# Connect.net
KiCad netlist of a schematic drawn in Altium Designer
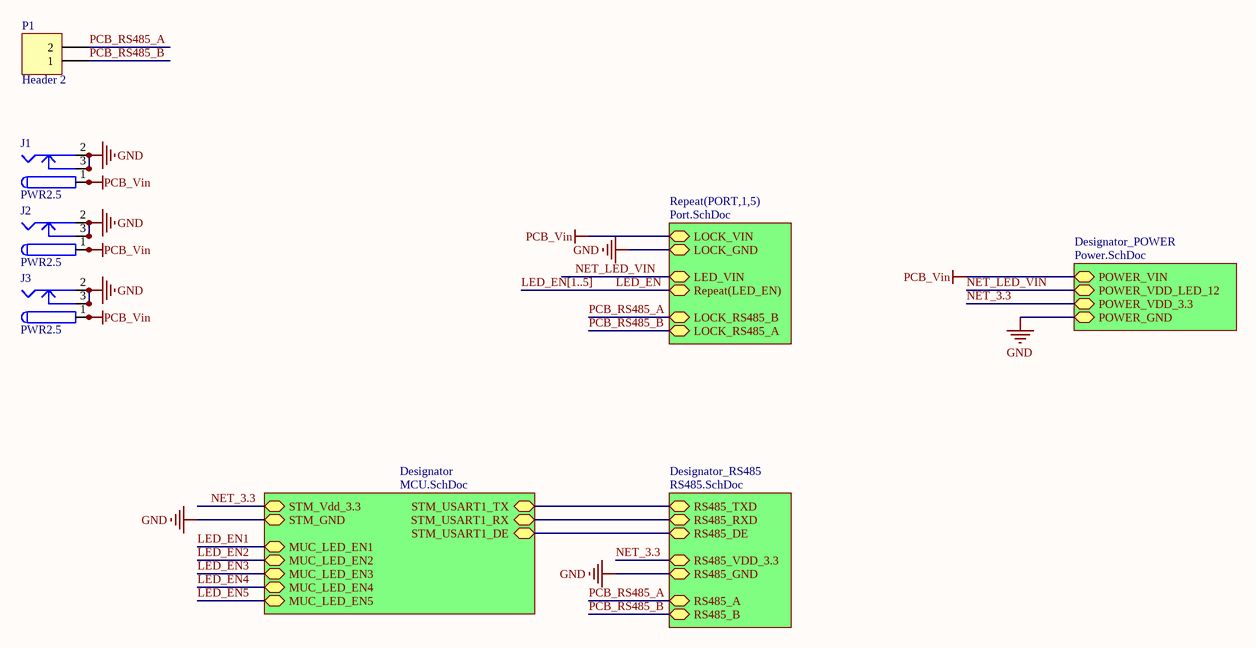
[diagram p0: Connect.SchDoc]

(export (version "E")
  (design (tool "Eeschema 10.0.6"))
  (components
    (comp (ref "J1")
      (value "PWR2.5")
      (footprint "KLD-0202")
      (description "Low Voltage Power Supply Connector")
      (fields (field (name "PUBLISHER") "Altium Limited"))
      (libsource (lib "Miscellaneous Connectors") (part "PWR2.5"))
    )
    (comp (ref "J2")
      (value "PWR2.5")
      (footprint "KLD-0202")
      (description "Low Voltage Power Supply Connector")
      (fields (field (name "PUBLISHER") "Altium Limited"))
      (libsource (lib "Miscellaneous Connectors") (part "PWR2.5"))
    )
    (comp (ref "J3")
      (value "PWR2.5")
      (footprint "KLD-0202")
      (description "Low Voltage Power Supply Connector")
      (fields (field (name "PUBLISHER") "Altium Limited"))
      (libsource (lib "Miscellaneous Connectors") (part "PWR2.5"))
    )
    (comp (ref "P1")
      (value "Header 2")
      (footprint "KF128-2P")
      (description "Header, 2-Pin")
      (fields (field (name "PUBLISHER") "Altium Limited"))
      (libsource (lib "Miscellaneous Connectors") (part "Header 2"))
    )
  )
  (nets
    (net (code "10") (name "/PCB_RS485_A") (class "Default")
      (node (ref "P1") (pin "2") (pinfunction "2_2") (pintype "passive"))
    )
    (net (code "11") (name "/PCB_RS485_B") (class "Default")
      (node (ref "P1") (pin "1") (pinfunction "1_1") (pintype "passive"))
    )
    (net (code "15") (name "GND") (class "Default")
      (node (ref "J1") (pin "2") (pinfunction "2_2") (pintype "power_in"))
      (node (ref "J1") (pin "2A") (pinfunction "2A_2A") (pintype "power_in"))
      (node (ref "J1") (pin "2B") (pinfunction "2B_2B") (pintype "power_in"))
      (node (ref "J1") (pin "3") (pinfunction "3_3") (pintype "power_in"))
      (node (ref "J1") (pin "3A") (pinfunction "3A_3A") (pintype "power_in"))
      (node (ref "J1") (pin "3B") (pinfunction "3B_3B") (pintype "power_in"))
      (node (ref "J2") (pin "2") (pinfunction "2_2") (pintype "power_in"))
      (node (ref "J2") (pin "2A") (pinfunction "2A_2A") (pintype "power_in"))
      (node (ref "J2") (pin "2B") (pinfunction "2B_2B") (pintype "power_in"))
      (node (ref "J2") (pin "3") (pinfunction "3_3") (pintype "power_in"))
      (node (ref "J2") (pin "3A") (pinfunction "3A_3A") (pintype "power_in"))
      (node (ref "J2") (pin "3B") (pinfunction "3B_3B") (pintype "power_in"))
      (node (ref "J3") (pin "2") (pinfunction "2_2") (pintype "power_in"))
      (node (ref "J3") (pin "2A") (pinfunction "2A_2A") (pintype "power_in"))
      (node (ref "J3") (pin "2B") (pinfunction "2B_2B") (pintype "power_in"))
      (node (ref "J3") (pin "3") (pinfunction "3_3") (pintype "power_in"))
      (node (ref "J3") (pin "3A") (pinfunction "3A_3A") (pintype "power_in"))
      (node (ref "J3") (pin "3B") (pinfunction "3B_3B") (pintype "power_in"))
    )
    (net (code "16") (name "PCB_Vin") (class "Default")
      (node (ref "J1") (pin "1") (pinfunction "1_1") (pintype "power_in"))
      (node (ref "J1") (pin "1A") (pinfunction "1A_1A") (pintype "power_in"))
      (node (ref "J1") (pin "1B") (pinfunction "1B_1B") (pintype "power_in"))
      (node (ref "J2") (pin "1") (pinfunction "1_1") (pintype "power_in"))
      (node (ref "J2") (pin "1A") (pinfunction "1A_1A") (pintype "power_in"))
      (node (ref "J2") (pin "1B") (pinfunction "1B_1B") (pintype "power_in"))
      (node (ref "J3") (pin "1") (pinfunction "1_1") (pintype "power_in"))
      (node (ref "J3") (pin "1A") (pinfunction "1A_1A") (pintype "power_in"))
      (node (ref "J3") (pin "1B") (pinfunction "1B_1B") (pintype "power_in"))
    )
  )
)
